# 5_-CONNECTORS.net
KiCad netlist of a schematic drawn in Altium Designer
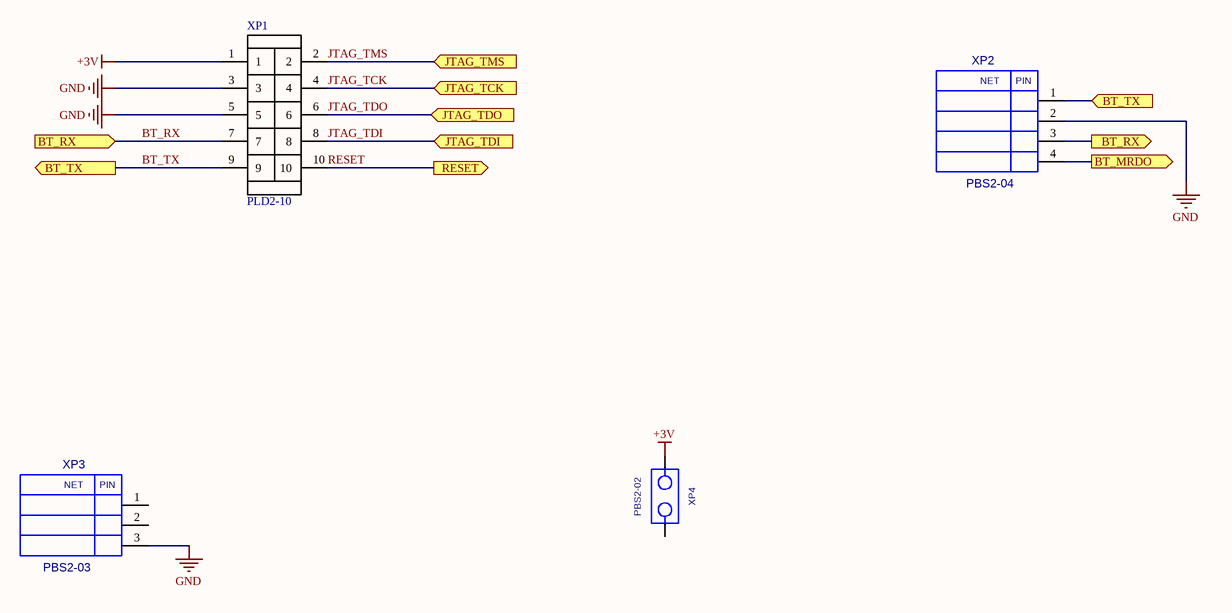
[diagram p0: [5]-CONNECTORS.SchDoc]

(export (version "E")
  (design (tool "Eeschema 10.0.6"))
  (components
    (comp (ref "XP1")
      (value "PLD2-10")
      (footprint "PLD2-10")
      (libsource (lib "gprs_modem_2") (part "PLD2-10"))
    )
    (comp (ref "XP2")
      (value "PBS2-04")
      (footprint "PLS2-04")
      (description "PLS2-04")
      (libsource (lib "gprs_modem_2") (part "PLS2-04"))
    )
    (comp (ref "XP3")
      (value "PBS2-03")
      (footprint "PLS2-03")
      (libsource (lib "gprs_modem_2") (part "PLS2-03"))
    )
    (comp (ref "XP4")
      (value "PBS2-02")
      (footprint "PLS2-02")
      (libsource (lib "gprs_modem_2") (part "PLS2-02"))
    )
  )
  (nets
    (net (code "1") (name "+3V") (class "Default")
      (node (ref "XP1") (pin "1") (pinfunction "1_1") (pintype "passive"))
      (node (ref "XP4") (pin "1") (pintype "passive"))
    )
    (net (code "2") (name "/BT_MRDO") (class "Default")
      (node (ref "XP2") (pin "4") (pinfunction "4_4") (pintype "passive"))
    )
    (net (code "3") (name "/BT_RX") (class "Default")
      (node (ref "XP1") (pin "7") (pinfunction "7_7") (pintype "passive"))
      (node (ref "XP2") (pin "3") (pinfunction "3_3") (pintype "passive"))
    )
    (net (code "4") (name "/BT_TX") (class "Default")
      (node (ref "XP1") (pin "9") (pinfunction "9_9") (pintype "passive"))
      (node (ref "XP2") (pin "1") (pinfunction "1_1") (pintype "passive"))
    )
    (net (code "5") (name "/JTAG_TCK") (class "Default")
      (node (ref "XP1") (pin "4") (pinfunction "4_4") (pintype "passive"))
    )
    (net (code "6") (name "/JTAG_TDI") (class "Default")
      (node (ref "XP1") (pin "8") (pinfunction "8_8") (pintype "passive"))
    )
    (net (code "7") (name "/JTAG_TDO") (class "Default")
      (node (ref "XP1") (pin "6") (pinfunction "6_6") (pintype "passive"))
    )
    (net (code "8") (name "/JTAG_TMS") (class "Default")
      (node (ref "XP1") (pin "2") (pinfunction "2_2") (pintype "passive"))
    )
    (net (code "9") (name "/RESET") (class "Default")
      (node (ref "XP1") (pin "10") (pinfunction "10_10") (pintype "passive"))
    )
    (net (code "10") (name "GND") (class "Default")
      (node (ref "XP1") (pin "3") (pinfunction "3_3") (pintype "passive"))
      (node (ref "XP1") (pin "5") (pinfunction "5_5") (pintype "passive"))
      (node (ref "XP2") (pin "2") (pinfunction "2_2") (pintype "passive"))
      (node (ref "XP3") (pin "3") (pinfunction "3_3") (pintype "passive"))
    )
    (net (code "11") (name "unconnected-(XP3-Pad1)") (class "Default")
      (node (ref "XP3") (pin "1") (pinfunction "1_1") (pintype "passive"))
    )
    (net (code "12") (name "unconnected-(XP3-Pad2)") (class "Default")
      (node (ref "XP3") (pin "2") (pinfunction "2_2") (pintype "passive"))
    )
    (net (code "13") (name "unconnected-(XP4-Pad2)") (class "Default")
      (node (ref "XP4") (pin "2") (pintype "passive"))
    )
  )
)
